# SparkFun_Rotary_Encoder-Illuminated.net
KiCad netlist of a schematic drawn in EAGLE
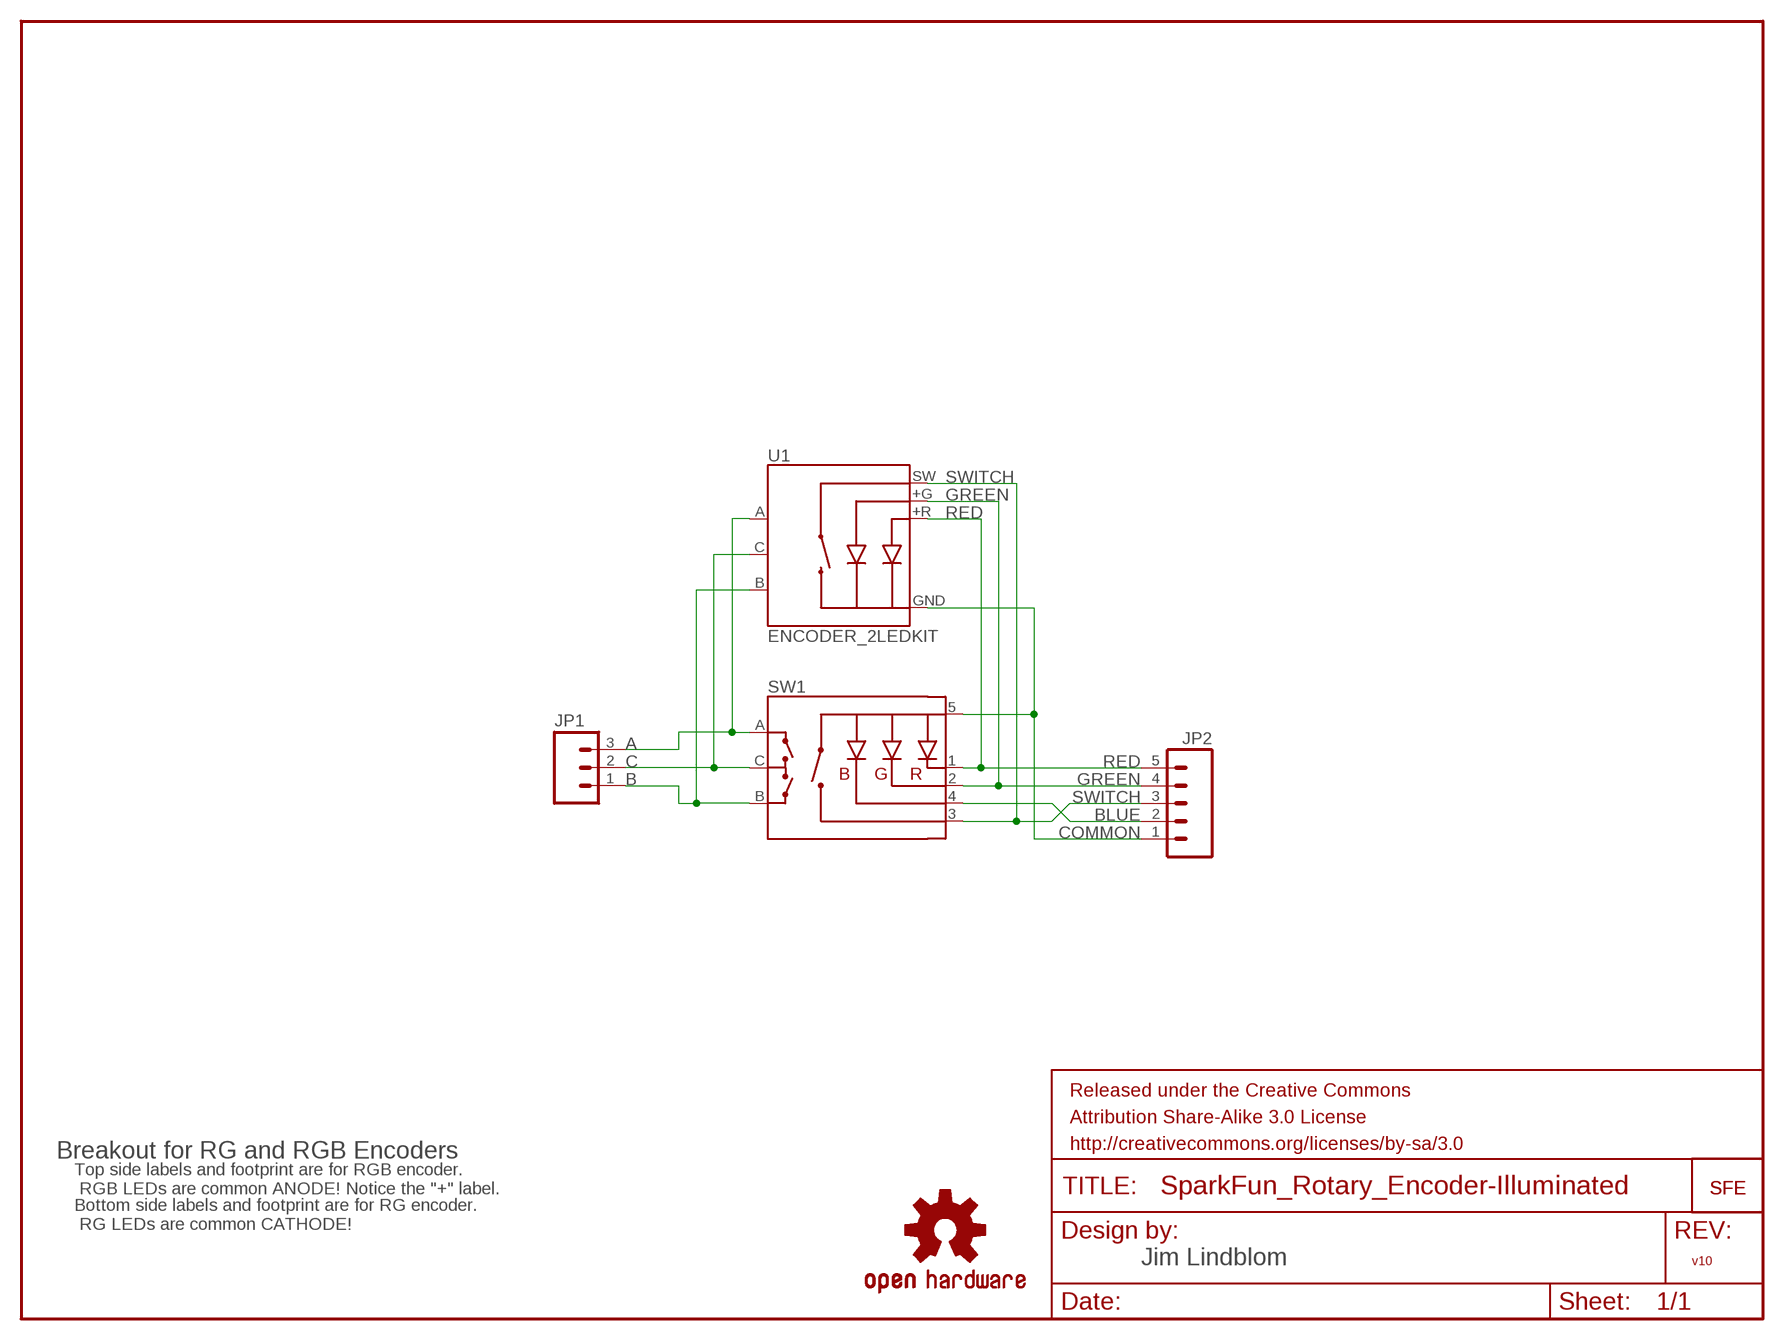
[diagram p0: schematic, sheet 1]

(export (version "E")
  (design (tool "Eeschema 10.0.6"))
  (components
    (comp (ref "FRAME1")
      (value "FRAME-LETTER")
      (footprint "eagle-import:CREATIVE_COMMONS")
      (libsource (lib "eagle-import") (part "FRAME-LETTER"))
    )
    (comp (ref "JP1")
      (value "M03PTH")
      (footprint "eagle-import:1X03")
      (libsource (lib "eagle-import") (part "M03PTH"))
    )
    (comp (ref "JP2")
      (value "M05PTH")
      (footprint "eagle-import:1X05")
      (libsource (lib "eagle-import") (part "M05PTH"))
    )
    (comp (ref "JP3")
      (value "LOGO-SFESK")
      (footprint "eagle-import:SFE-LOGO-FLAME")
      (libsource (lib "eagle-import") (part "LOGO-SFESK"))
    )
    (comp (ref "JP4")
      (value "LOGO-SFESK")
      (footprint "eagle-import:SFE-LOGO-FLAME")
      (libsource (lib "eagle-import") (part "LOGO-SFESK"))
    )
    (comp (ref "SW1")
      (value "ENCODER_RGB_CAKIT")
      (footprint "eagle-import:ENCODER_LED_3_KIT")
      (libsource (lib "eagle-import") (part "ENCODER_RGB_CAKIT"))
    )
    (comp (ref "U$2")
      (value "OSHW-LOGOS")
      (footprint "eagle-import:OSHW-LOGO-S")
      (libsource (lib "eagle-import") (part "OSHW-LOGOS"))
    )
    (comp (ref "U1")
      (value "ENCODER_2LEDKIT")
      (footprint "eagle-import:ENCODER_LED_2_KIT")
      (libsource (lib "eagle-import") (part "ENCODER_2LEDKIT"))
    )
  )
  (nets
    (net (code "1") (name "/A") (class "Default")
      (node (ref "JP1") (pin "3") (pinfunction "3_3") (pintype "passive"))
      (node (ref "SW1") (pin "A") (pinfunction "A_A") (pintype "bidirectional"))
      (node (ref "U1") (pin "A") (pinfunction "A_A") (pintype "bidirectional"))
    )
    (net (code "2") (name "/B") (class "Default")
      (node (ref "JP1") (pin "1") (pinfunction "1_1") (pintype "passive"))
      (node (ref "SW1") (pin "B") (pinfunction "B_B") (pintype "bidirectional"))
      (node (ref "U1") (pin "B") (pinfunction "B_B") (pintype "bidirectional"))
    )
    (net (code "3") (name "/BLUE") (class "Default")
      (node (ref "JP2") (pin "2") (pinfunction "2_2") (pintype "passive"))
      (node (ref "SW1") (pin "4") (pinfunction "-B_4") (pintype "passive"))
    )
    (net (code "4") (name "/C") (class "Default")
      (node (ref "JP1") (pin "2") (pinfunction "2_2") (pintype "passive"))
      (node (ref "SW1") (pin "C") (pinfunction "C_C") (pintype "bidirectional"))
      (node (ref "U1") (pin "C") (pinfunction "C_C") (pintype "bidirectional"))
    )
    (net (code "5") (name "/COMMON") (class "Default")
      (node (ref "JP2") (pin "1") (pinfunction "1_1") (pintype "passive"))
      (node (ref "SW1") (pin "5") (pinfunction "+_5") (pintype "passive"))
      (node (ref "U1") (pin "GND") (pinfunction "-_GND") (pintype "passive"))
    )
    (net (code "6") (name "/GREEN") (class "Default")
      (node (ref "JP2") (pin "4") (pinfunction "4_4") (pintype "passive"))
      (node (ref "SW1") (pin "2") (pinfunction "-G_2") (pintype "passive"))
      (node (ref "U1") (pin "+G") (pinfunction "+G_+G") (pintype "passive"))
    )
    (net (code "7") (name "/RED") (class "Default")
      (node (ref "JP2") (pin "5") (pinfunction "5_5") (pintype "passive"))
      (node (ref "SW1") (pin "1") (pinfunction "-R_1") (pintype "passive"))
      (node (ref "U1") (pin "+R") (pinfunction "+R_+R") (pintype "passive"))
    )
    (net (code "8") (name "/SWITCH") (class "Default")
      (node (ref "JP2") (pin "3") (pinfunction "3_3") (pintype "passive"))
      (node (ref "SW1") (pin "3") (pinfunction "SW_3") (pintype "passive"))
      (node (ref "U1") (pin "SW") (pinfunction "SW_SW") (pintype "passive"))
    )
  )
)
